# ESS.net
KiCad netlist of a schematic drawn in Altium Designer
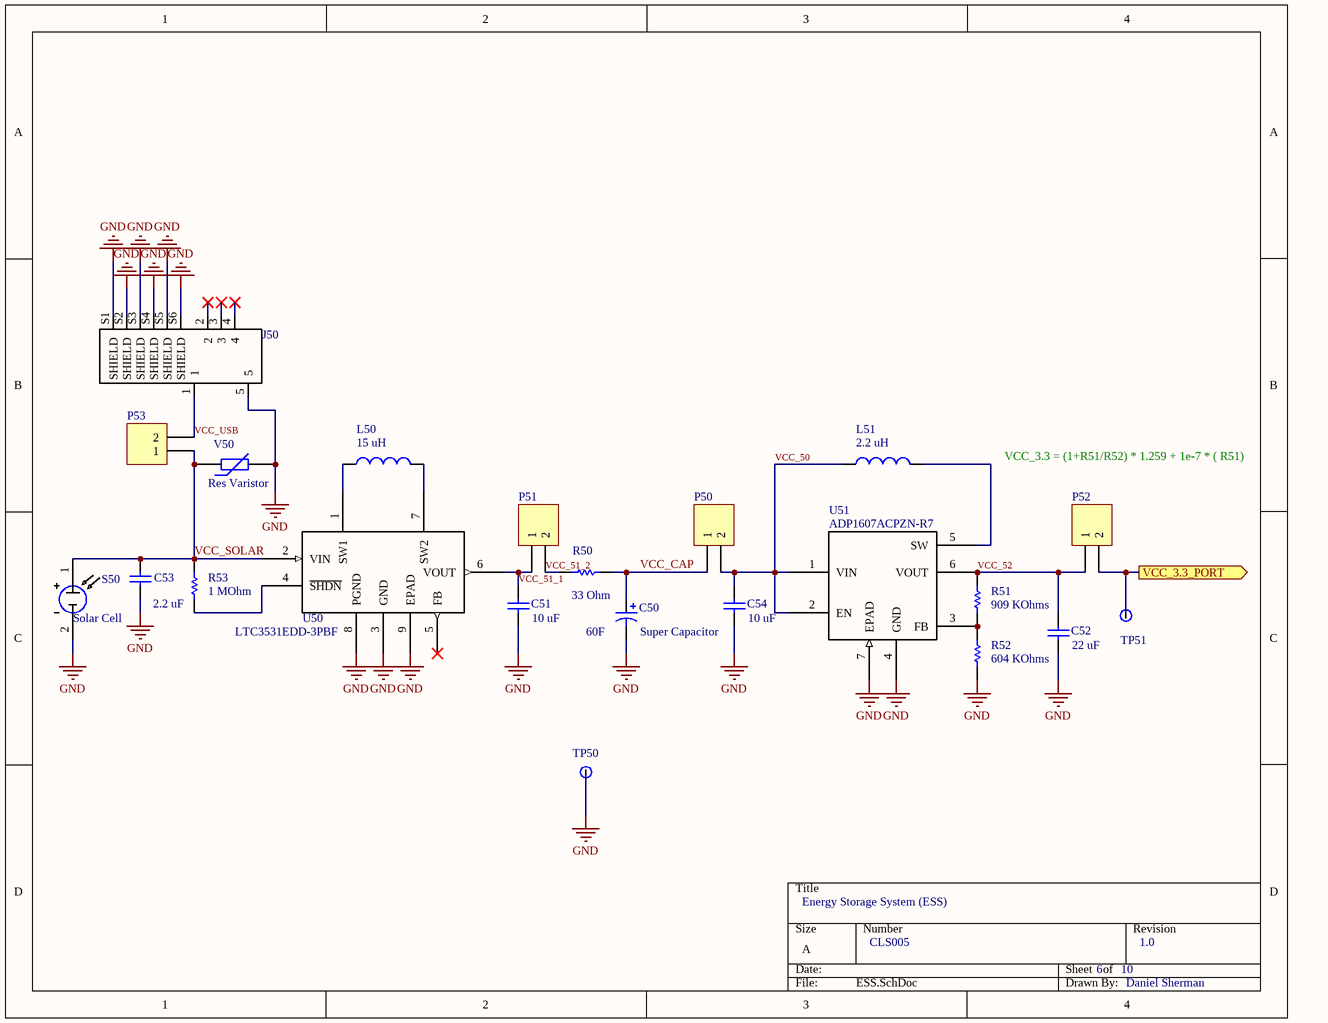
[diagram p0: ESS.SchDoc]

(export (version "E")
  (design (tool "Eeschema 10.0.6"))
  (components
    (comp (ref "C50")
      (value "Super Capacitor")
      (footprint "TV1840-3R0606-R")
      (fields
        (field (name "ALTIUM_VALUE") "60F")
        (field (name "MANUFACTURER") "Eaton")
        (field (name "MANUFACTURER PART NUMBER") "TV1840-3R0606-R")
      )
      (libsource (lib "GenericSymbols") (part "Capacitor Polarized"))
    )
    (comp (ref "C51")
      (value "10 uF")
      (footprint "0805_CHIP_FP")
      (fields
        (field (name "MANUFACTURER") "Samsung Electro-Mechanics")
        (field (name "MANUFACTURER PART NUMBER") "CL21A106KQCLRNC")
        (field (name "VENDOR PART NUMBER") "1276-2405-1-ND")
      )
      (libsource (lib "GenericSymbols") (part "Capacitor_unpolarized_0805"))
    )
    (comp (ref "C52")
      (value "22 uF")
      (footprint "0805_CHIP_FP")
      (fields
        (field (name "MANUFACTURER") "Samsung Electro-Mechanics")
        (field (name "MANUFACTURER PART NUMBER") "CL21A226MQQNNNE")
        (field (name "VENDOR PART NUMBER") "1276-1100-1-ND")
      )
      (libsource (lib "GenericSymbols") (part "Capacitor_unpolarized_0805"))
    )
    (comp (ref "C53")
      (value "2.2 uF")
      (footprint "0805_CHIP_FP")
      (fields
        (field (name "MANUFACTURER") "Wurth Electronics Inc.")
        (field (name "MANUFACTURER PART NUMBER") "885012107001")
        (field (name "VENDOR PART NUMBER") "732-7612-1-ND")
      )
      (libsource (lib "GenericSymbols") (part "Capacitor_unpolarized_0805"))
    )
    (comp (ref "C54")
      (value "10 uF")
      (footprint "0805_CHIP_FP")
      (fields
        (field (name "MANUFACTURER") "Samsung Electro-Mechanics")
        (field (name "MANUFACTURER PART NUMBER") "CL21A106KQCLRNC")
        (field (name "VENDOR PART NUMBER") "1276-2405-1-ND")
      )
      (libsource (lib "GenericSymbols") (part "Capacitor_unpolarized_0805"))
    )
    (comp (ref "J50")
      (value "2174507-2")
      (footprint "J_SMD_2174507-2-5_7.8_5_2.71_2174507-2(Primary)")
      (fields
        (field (name "MANUFACTURER") "TE Connectivity AMP Connectors")
        (field (name "VENDOR PART NUMBER") "A118106CT-ND")
      )
      (libsource (lib "2174507-2") (part "2174507-2"))
    )
    (comp (ref "L50")
      (value "15 uH")
      (footprint "1919")
      (fields
        (field (name "MANUFACTURER") "Wurth Electronics Inc.")
        (field (name "MANUFACTURER PART NUMBER") "744042150")
        (field (name "VENDOR PART NUMBER") "732-3655-1-ND")
      )
      (libsource (lib "GenericSymbols") (part "Inductor_0805"))
    )
    (comp (ref "L51")
      (value "2.2 uH")
      (footprint "0805_CHIP_FP")
      (fields
        (field (name "MANUFACTURER") "Taiyo Yuden")
        (field (name "MANUFACTURER PART NUMBER") "BRC2012T2R2MD")
        (field (name "VENDOR PART NUMBER") "587-2905-1-ND")
      )
      (libsource (lib "GenericSymbols") (part "Inductor_0805"))
    )
    (comp (ref "P50")
      (value "Header 2H")
      (footprint "HDR1X2")
      (fields (field (name "VENDOR PART NUMBER") "PRT-00116"))
      (libsource (lib "Miscellaneous Connectors") (part "Header 2H"))
    )
    (comp (ref "P51")
      (value "Header 2H")
      (footprint "HDR1X2")
      (fields (field (name "VENDOR PART NUMBER") "PRT-00116"))
      (libsource (lib "Miscellaneous Connectors") (part "Header 2H"))
    )
    (comp (ref "P52")
      (value "Header 2H")
      (footprint "HDR1X2")
      (fields (field (name "VENDOR PART NUMBER") "PRT-00116"))
      (libsource (lib "Miscellaneous Connectors") (part "Header 2H"))
    )
    (comp (ref "P53")
      (value "Header 2H")
      (footprint "HDR1X2")
      (fields (field (name "VENDOR PART NUMBER") "PRT-00116"))
      (libsource (lib "") (part "Header 2H_1"))
    )
    (comp (ref "R50")
      (value "33 Ohm")
      (footprint "0805_CHIP_FP")
      (fields
        (field (name "MANUFACTURER") "Panasonic Electronic Components")
        (field (name "MANUFACTURER PART NUMBER") "ERJ-P06J330V")
        (field (name "VENDOR PART NUMBER") "P33ADCT-ND")
      )
      (libsource (lib "GenericSymbols") (part "Resistor_0805"))
    )
    (comp (ref "R51")
      (value "909 KOhms")
      (footprint "0805_CHIP_FP")
      (fields
        (field (name "MANUFACTURER") "Yageo")
        (field (name "MANUFACTURER PART NUMBER") "RC0805FR-07909KL")
        (field (name "VENDOR PART NUMBER") "311-909KCRCT-ND")
      )
      (libsource (lib "GenericSymbols") (part "Resistor_0805"))
    )
    (comp (ref "R52")
      (value "604 KOhms")
      (footprint "0805_CHIP_FP")
      (fields
        (field (name "MANUFACTURER") "Yageo")
        (field (name "MANUFACTURER PART NUMBER") "RC0805FR-07604KL")
        (field (name "VENDOR PART NUMBER") "311-604KCRCT-ND")
      )
      (libsource (lib "GenericSymbols") (part "Resistor_0805"))
    )
    (comp (ref "R53")
      (value "1 MOhm")
      (footprint "0805_CHIP_FP")
      (fields
        (field (name "MANUFACTURER") "Yageo")
        (field (name "MANUFACTURER PART NUMBER") "RC0805FR-071ML")
        (field (name "VENDOR PART NUMBER") "311-1.00MCRCT-ND")
      )
      (libsource (lib "GenericSymbols") (part "Resistor_0805"))
    )
    (comp (ref "S50")
      (value "Solar Cell")
      (footprint "HDR1X2")
      (description "IXOLAR SLMD121H08L")
      (fields (field (name "MANUFACTURER") "IXYS") (field (name "MANUFACTURER PART NUMBER") "SLMD121H08L"))
      (libsource (lib "GenericSymbols") (part "Solar Cell"))
    )
    (comp (ref "TP50")
      (value "Testpoint")
      (footprint "HDR1X1")
      (fields (field (name "MANUFACTURER") "Sparkfun") (field (name "VENDOR PART NUMBER") "PRT-00116"))
      (libsource (lib "Testpoint") (part "Testpoint"))
    )
    (comp (ref "TP51")
      (value "Testpoint")
      (footprint "HDR1X1")
      (fields (field (name "MANUFACTURER") "Sparkfun") (field (name "VENDOR PART NUMBER") "PRT-00116"))
      (libsource (lib "Testpoint") (part "Testpoint"))
    )
    (comp (ref "U50")
      (value "LTC3531EDD-3PBF")
      (footprint "DFN-8_DD")
      (description "LTC3531 - 200mA Buck-Boost Synchronous DC/DC Converters")
      (fields
        (field (name "MANUFACTURER") "Linear Technology")
        (field (name "VENDER PART NUMBER") "LTC3531EDD-3#PBF-ND")
      )
      (libsource (lib "LTC3531EDD-3PBF") (part "LTC3531EDD-3PBF"))
    )
    (comp (ref "U51")
      (value "ADP1607ACPZN-R7")
      (footprint "ADP1607")
      (fields
        (field (name "MANUFACTURER") "Analog Devices Inc.")
        (field (name "VENDOR PART NUMBER") "ADP1607ACPZN-R7CT-ND")
      )
      (libsource (lib "ADP1607") (part "ADP1607ACPZN-R7"))
    )
    (comp (ref "V50")
      (value "Res Varistor")
      (footprint "6-0805_N")
      (description "Varistor (Voltage-Sensitive Resistor)")
      (fields
        (field (name "MANUFACTURER") "Littelfuse Inc.")
        (field (name "MANUFACTURER PART NUMBER") "V5.5MLA0805NH")
      )
      (libsource (lib "Miscellaneous Devices") (part "Res Varistor"))
    )
  )
  (nets
    (net (code "1") (name "/VCC_3.3_PORT") (class "Default")
      (node (ref "P52") (pin "2") (pinfunction "2_2") (pintype "passive"))
      (node (ref "TP51") (pin "1") (pinfunction "OUT_1") (pintype "input"))
    )
    (net (code "2") (name "/VCC_50") (class "Default")
      (node (ref "C54") (pin "2") (pinfunction "2_2") (pintype "passive"))
      (node (ref "L51") (pin "1") (pinfunction "1_1") (pintype "passive"))
      (node (ref "P50") (pin "2") (pinfunction "2_2") (pintype "passive"))
      (node (ref "U51") (pin "1") (pinfunction "VIN_1") (pintype "power_in"))
      (node (ref "U51") (pin "2") (pinfunction "EN_2") (pintype "power_in"))
    )
    (net (code "3") (name "/VCC_51_1") (class "Default")
      (node (ref "C51") (pin "2") (pinfunction "2_2") (pintype "passive"))
      (node (ref "P51") (pin "1") (pinfunction "1_1") (pintype "passive"))
      (node (ref "U50") (pin "6") (pinfunction "VOUT_6") (pintype "output"))
    )
    (net (code "4") (name "/VCC_51_2") (class "Default")
      (node (ref "P51") (pin "2") (pinfunction "2_2") (pintype "passive"))
      (node (ref "R50") (pin "1") (pinfunction "1_1") (pintype "passive"))
    )
    (net (code "5") (name "/VCC_52") (class "Default")
      (node (ref "C52") (pin "2") (pinfunction "2_2") (pintype "passive"))
      (node (ref "P52") (pin "1") (pinfunction "1_1") (pintype "passive"))
      (node (ref "R51") (pin "2") (pinfunction "2_2") (pintype "passive"))
      (node (ref "U51") (pin "6") (pinfunction "VOUT_6") (pintype "power_in"))
    )
    (net (code "6") (name "/VCC_CAP") (class "Default")
      (node (ref "C50") (pin "1") (pinfunction "1_1") (pintype "passive"))
      (node (ref "P50") (pin "1") (pinfunction "1_1") (pintype "passive"))
      (node (ref "R50") (pin "2") (pinfunction "2_2") (pintype "passive"))
    )
    (net (code "7") (name "/VCC_SOLAR") (class "Default")
      (node (ref "C53") (pin "2") (pinfunction "2_2") (pintype "passive"))
      (node (ref "P53") (pin "1") (pinfunction "1_1") (pintype "passive"))
      (node (ref "R53") (pin "2") (pinfunction "2_2") (pintype "passive"))
      (node (ref "S50") (pin "1") (pintype "power_in"))
      (node (ref "U50") (pin "2") (pinfunction "VIN_2") (pintype "input"))
      (node (ref "V50") (pin "1") (pinfunction "1_1") (pintype "passive"))
    )
    (net (code "8") (name "/VCC_USB") (class "Default")
      (node (ref "J50") (pin "1") (pinfunction "1_1") (pintype "passive"))
      (node (ref "P53") (pin "2") (pinfunction "2_2") (pintype "passive"))
    )
    (net (code "9") (name "GND") (class "Default")
      (node (ref "C50") (pin "2") (pinfunction "2_2") (pintype "passive"))
      (node (ref "C51") (pin "1") (pinfunction "1_1") (pintype "passive"))
      (node (ref "C52") (pin "1") (pinfunction "1_1") (pintype "passive"))
      (node (ref "C53") (pin "1") (pinfunction "1_1") (pintype "passive"))
      (node (ref "C54") (pin "1") (pinfunction "1_1") (pintype "passive"))
      (node (ref "J50") (pin "5") (pinfunction "5_5") (pintype "passive"))
      (node (ref "J50") (pin "S1") (pinfunction "SHIELD_S1") (pintype "passive"))
      (node (ref "J50") (pin "S2") (pinfunction "SHIELD_S2") (pintype "passive"))
      (node (ref "J50") (pin "S3") (pinfunction "SHIELD_S3") (pintype "passive"))
      (node (ref "J50") (pin "S4") (pinfunction "SHIELD_S4") (pintype "passive"))
      (node (ref "J50") (pin "S5") (pinfunction "SHIELD_S5") (pintype "passive"))
      (node (ref "J50") (pin "S6") (pinfunction "SHIELD_S6") (pintype "passive"))
      (node (ref "R52") (pin "1") (pinfunction "1_1") (pintype "passive"))
      (node (ref "S50") (pin "2") (pintype "power_in"))
      (node (ref "TP50") (pin "1") (pinfunction "OUT_1") (pintype "input"))
      (node (ref "U50") (pin "3") (pinfunction "GND_3") (pintype "power_in"))
      (node (ref "U50") (pin "8") (pinfunction "PGND_8") (pintype "power_in"))
      (node (ref "U50") (pin "9") (pinfunction "EPAD_9") (pintype "passive"))
      (node (ref "U51") (pin "4") (pinfunction "GND_4") (pintype "power_in"))
      (node (ref "U51") (pin "7") (pinfunction "EPAD_7") (pintype "input"))
      (node (ref "V50") (pin "2") (pinfunction "2_2") (pintype "passive"))
    )
    (net (code "10") (name "Net-(U50-SW1)") (class "Default")
      (node (ref "L50") (pin "1") (pinfunction "1_1") (pintype "passive"))
      (node (ref "U50") (pin "1") (pinfunction "SW1_1") (pintype "passive"))
    )
    (net (code "11") (name "Net-(U50-SW2)") (class "Default")
      (node (ref "L50") (pin "2") (pinfunction "2_2") (pintype "passive"))
      (node (ref "U50") (pin "7") (pinfunction "SW2_7") (pintype "passive"))
    )
    (net (code "12") (name "Net-(U50-~{SHDN})") (class "Default")
      (node (ref "R53") (pin "1") (pinfunction "1_1") (pintype "passive"))
      (node (ref "U50") (pin "4") (pinfunction "~{SHDN}_4") (pintype "passive"))
    )
    (net (code "13") (name "Net-(U51-FB)") (class "Default")
      (node (ref "R51") (pin "1") (pinfunction "1_1") (pintype "passive"))
      (node (ref "R52") (pin "2") (pinfunction "2_2") (pintype "passive"))
      (node (ref "U51") (pin "3") (pinfunction "FB_3") (pintype "power_in"))
    )
    (net (code "14") (name "Net-(U51-SW)") (class "Default")
      (node (ref "L51") (pin "2") (pinfunction "2_2") (pintype "passive"))
      (node (ref "U51") (pin "5") (pinfunction "SW_5") (pintype "power_in"))
    )
    (net (code "15") (name "unconnected-(J50-Pad2)") (class "Default")
      (node (ref "J50") (pin "2") (pinfunction "2_2") (pintype "passive+no_connect"))
    )
    (net (code "16") (name "unconnected-(J50-Pad3)") (class "Default")
      (node (ref "J50") (pin "3") (pinfunction "3_3") (pintype "passive+no_connect"))
    )
    (net (code "17") (name "unconnected-(J50-Pad4)") (class "Default")
      (node (ref "J50") (pin "4") (pinfunction "4_4") (pintype "passive+no_connect"))
    )
    (net (code "18") (name "unconnected-(U50-FB-Pad5)") (class "Default")
      (node (ref "U50") (pin "5") (pinfunction "FB_5") (pintype "output+no_connect"))
    )
  )
)
